# di.net
KiCad netlist of a schematic drawn in Altium Designer
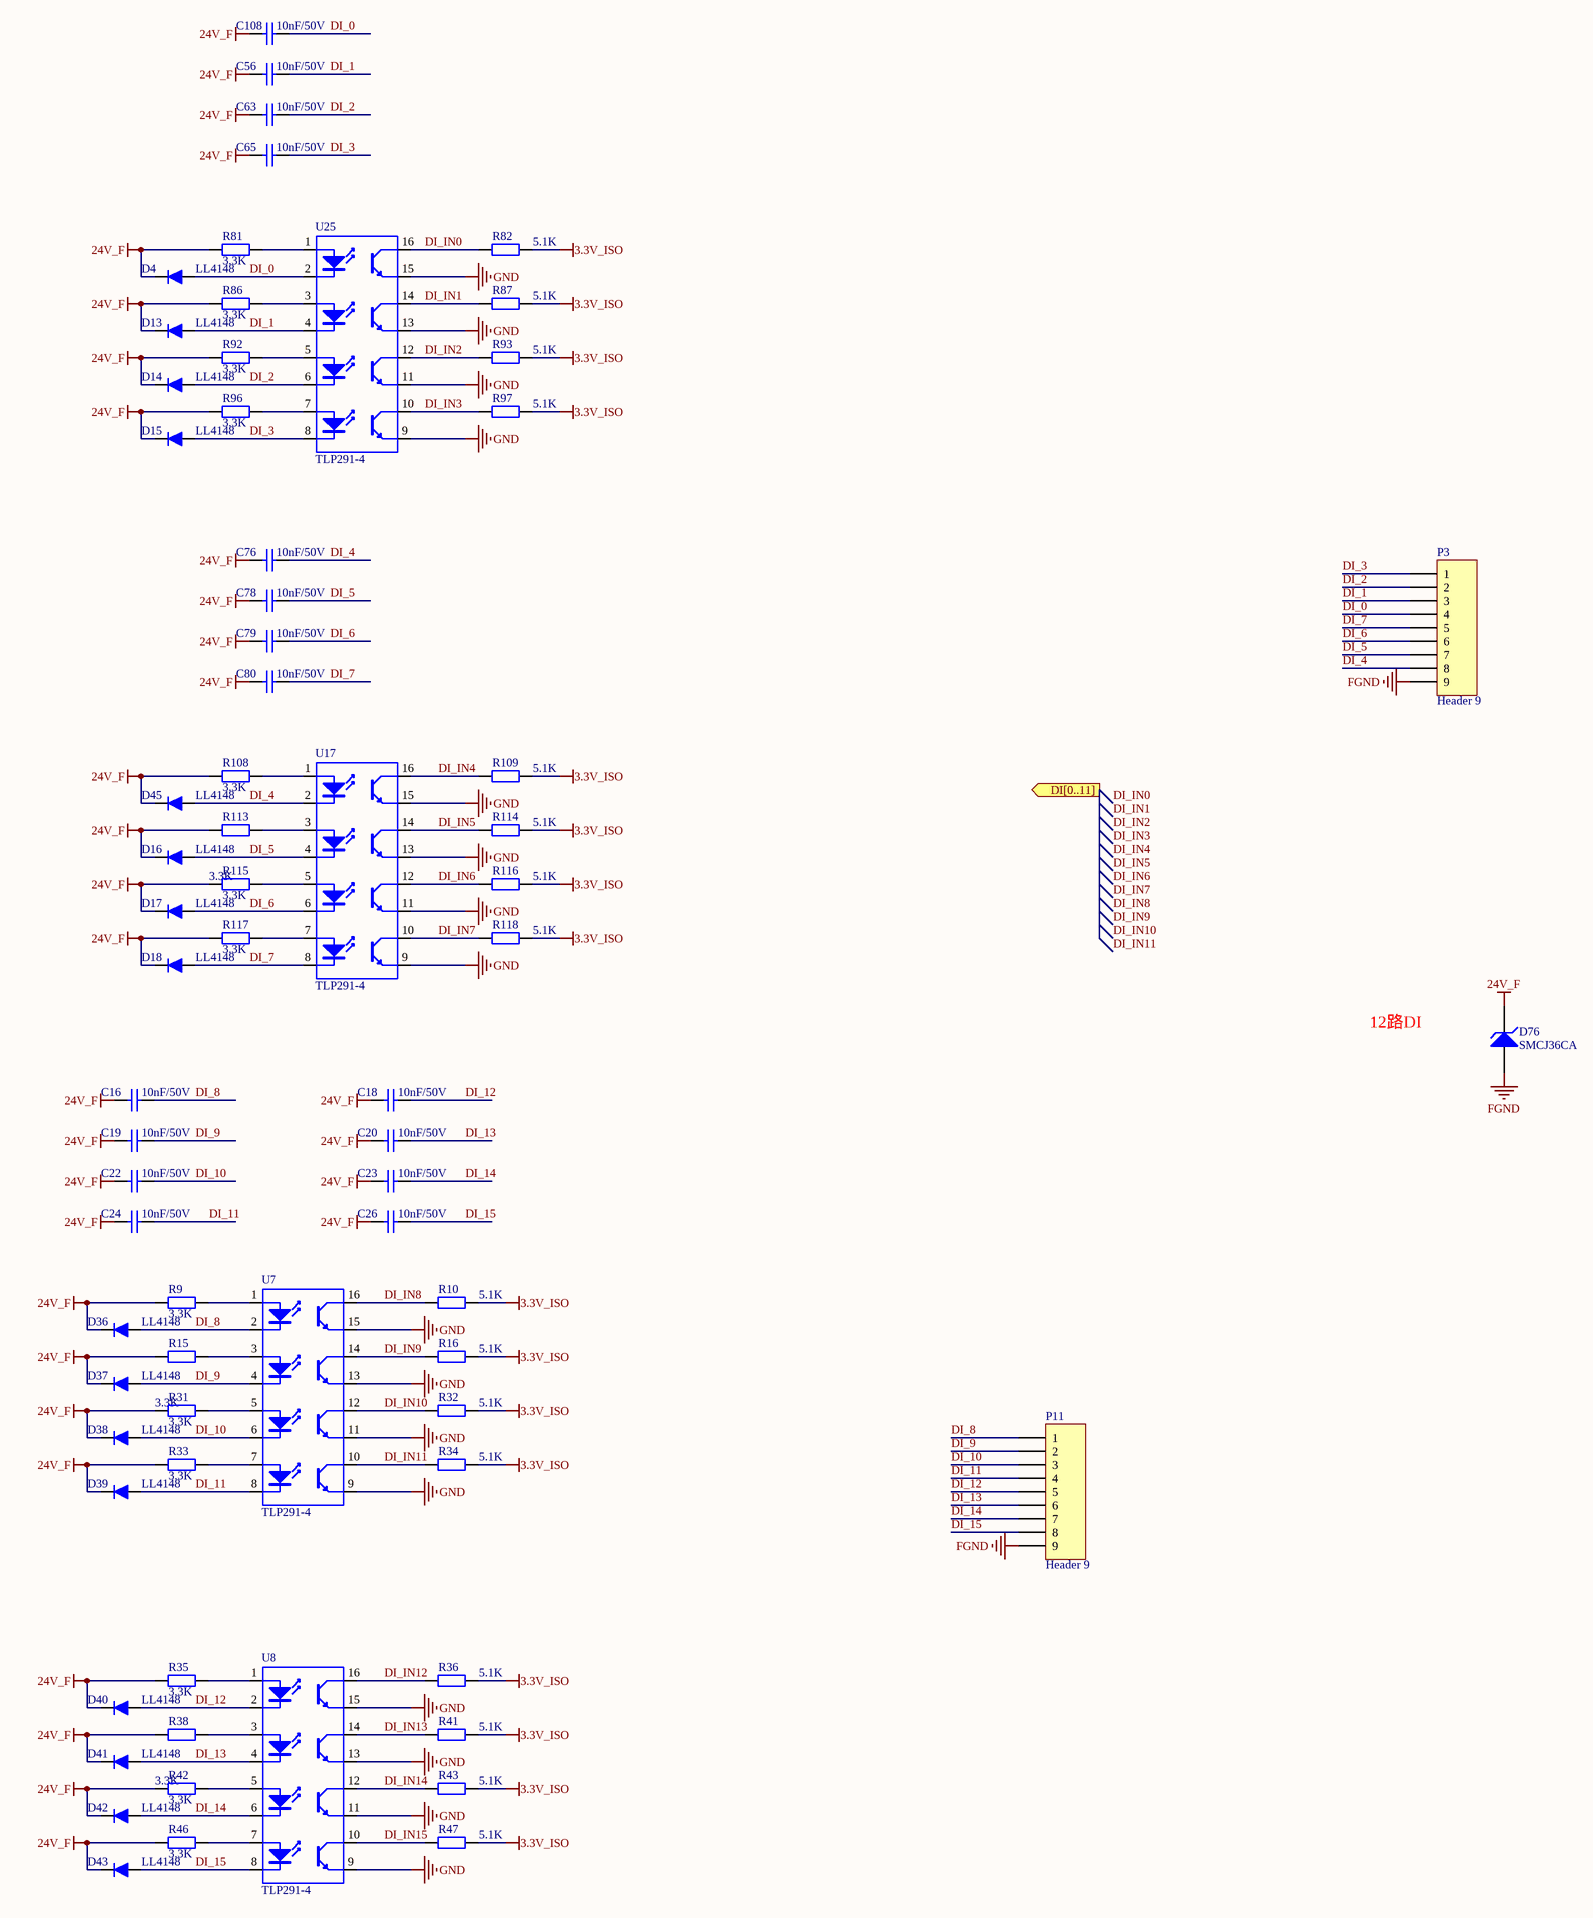
[diagram p0: di.SchDoc]

(export (version "E")
  (design (tool "Eeschema 10.0.6"))
  (components
    (comp (ref "C16")
      (value "10nF/50V")
      (footprint "0603C")
      (description "Capacitor")
      (fields (field (name "PUBLISHER") "Altium Limited"))
      (libsource (lib "Miscellaneous Devices") (part "Cap"))
    )
    (comp (ref "C18")
      (value "10nF/50V")
      (footprint "0603C")
      (description "Capacitor")
      (fields (field (name "PUBLISHER") "Altium Limited"))
      (libsource (lib "Miscellaneous Devices") (part "Cap"))
    )
    (comp (ref "C19")
      (value "10nF/50V")
      (footprint "0603C")
      (description "Capacitor")
      (fields (field (name "PUBLISHER") "Altium Limited"))
      (libsource (lib "Miscellaneous Devices") (part "Cap"))
    )
    (comp (ref "C20")
      (value "10nF/50V")
      (footprint "0603C")
      (description "Capacitor")
      (fields (field (name "PUBLISHER") "Altium Limited"))
      (libsource (lib "Miscellaneous Devices") (part "Cap"))
    )
    (comp (ref "C22")
      (value "10nF/50V")
      (footprint "0603C")
      (description "Capacitor")
      (fields (field (name "PUBLISHER") "Altium Limited"))
      (libsource (lib "Miscellaneous Devices") (part "Cap"))
    )
    (comp (ref "C23")
      (value "10nF/50V")
      (footprint "0603C")
      (description "Capacitor")
      (fields (field (name "PUBLISHER") "Altium Limited"))
      (libsource (lib "Miscellaneous Devices") (part "Cap"))
    )
    (comp (ref "C24")
      (value "10nF/50V")
      (footprint "0603C")
      (description "Capacitor")
      (fields (field (name "PUBLISHER") "Altium Limited"))
      (libsource (lib "Miscellaneous Devices") (part "Cap"))
    )
    (comp (ref "C26")
      (value "10nF/50V")
      (footprint "0603C")
      (description "Capacitor")
      (fields (field (name "PUBLISHER") "Altium Limited"))
      (libsource (lib "Miscellaneous Devices") (part "Cap"))
    )
    (comp (ref "C56")
      (value "10nF/50V")
      (footprint "0603C")
      (description "Capacitor")
      (fields (field (name "PUBLISHER") "Altium Limited"))
      (libsource (lib "Miscellaneous Devices") (part "Cap"))
    )
    (comp (ref "C63")
      (value "10nF/50V")
      (footprint "0603C")
      (description "Capacitor")
      (fields (field (name "PUBLISHER") "Altium Limited"))
      (libsource (lib "Miscellaneous Devices") (part "Cap"))
    )
    (comp (ref "C65")
      (value "10nF/50V")
      (footprint "0603C")
      (description "Capacitor")
      (fields (field (name "PUBLISHER") "Altium Limited"))
      (libsource (lib "Miscellaneous Devices") (part "Cap"))
    )
    (comp (ref "C76")
      (value "10nF/50V")
      (footprint "0603C")
      (description "Capacitor")
      (fields (field (name "PUBLISHER") "Altium Limited"))
      (libsource (lib "Miscellaneous Devices") (part "Cap"))
    )
    (comp (ref "C78")
      (value "10nF/50V")
      (footprint "0603C")
      (description "Capacitor")
      (fields (field (name "PUBLISHER") "Altium Limited"))
      (libsource (lib "Miscellaneous Devices") (part "Cap"))
    )
    (comp (ref "C79")
      (value "10nF/50V")
      (footprint "0603C")
      (description "Capacitor")
      (fields (field (name "PUBLISHER") "Altium Limited"))
      (libsource (lib "Miscellaneous Devices") (part "Cap"))
    )
    (comp (ref "C80")
      (value "10nF/50V")
      (footprint "0603C")
      (description "Capacitor")
      (fields (field (name "PUBLISHER") "Altium Limited"))
      (libsource (lib "Miscellaneous Devices") (part "Cap"))
    )
    (comp (ref "C108")
      (value "10nF/50V")
      (footprint "0603C")
      (description "Capacitor")
      (fields (field (name "PUBLISHER") "Altium Limited"))
      (libsource (lib "Miscellaneous Devices") (part "Cap"))
    )
    (comp (ref "D4")
      (value "LL4148")
      (footprint "DO-213AB/LL34/MiniMELF")
      (description "VISHAY,LL4148,圆柱体MiniMELF100V/2A,ROHS")
      (libsource (lib "Device2018") (part "LL4148"))
    )
    (comp (ref "D13")
      (value "LL4148")
      (footprint "DO-213AB/LL34/MiniMELF")
      (description "VISHAY,LL4148,圆柱体MiniMELF100V/2A,ROHS")
      (libsource (lib "Device2018") (part "LL4148"))
    )
    (comp (ref "D14")
      (value "LL4148")
      (footprint "DO-213AB/LL34/MiniMELF")
      (description "VISHAY,LL4148,圆柱体MiniMELF100V/2A,ROHS")
      (libsource (lib "Device2018") (part "LL4148"))
    )
    (comp (ref "D15")
      (value "LL4148")
      (footprint "DO-213AB/LL34/MiniMELF")
      (description "VISHAY,LL4148,圆柱体MiniMELF100V/2A,ROHS")
      (libsource (lib "Device2018") (part "LL4148"))
    )
    (comp (ref "D16")
      (value "LL4148")
      (footprint "DO-213AB/LL34/MiniMELF")
      (description "VISHAY,LL4148,圆柱体MiniMELF100V/2A,ROHS")
      (libsource (lib "Device2018") (part "LL4148"))
    )
    (comp (ref "D17")
      (value "LL4148")
      (footprint "DO-213AB/LL34/MiniMELF")
      (description "VISHAY,LL4148,圆柱体MiniMELF100V/2A,ROHS")
      (libsource (lib "Device2018") (part "LL4148"))
    )
    (comp (ref "D18")
      (value "LL4148")
      (footprint "DO-213AB/LL34/MiniMELF")
      (description "VISHAY,LL4148,圆柱体MiniMELF100V/2A,ROHS")
      (libsource (lib "Device2018") (part "LL4148"))
    )
    (comp (ref "D36")
      (value "LL4148")
      (footprint "DO-213AB/LL34/MiniMELF")
      (description "VISHAY,LL4148,圆柱体MiniMELF100V/2A,ROHS")
      (libsource (lib "Device2018") (part "LL4148"))
    )
    (comp (ref "D37")
      (value "LL4148")
      (footprint "DO-213AB/LL34/MiniMELF")
      (description "VISHAY,LL4148,圆柱体MiniMELF100V/2A,ROHS")
      (libsource (lib "Device2018") (part "LL4148"))
    )
    (comp (ref "D38")
      (value "LL4148")
      (footprint "DO-213AB/LL34/MiniMELF")
      (description "VISHAY,LL4148,圆柱体MiniMELF100V/2A,ROHS")
      (libsource (lib "Device2018") (part "LL4148"))
    )
    (comp (ref "D39")
      (value "LL4148")
      (footprint "DO-213AB/LL34/MiniMELF")
      (description "VISHAY,LL4148,圆柱体MiniMELF100V/2A,ROHS")
      (libsource (lib "Device2018") (part "LL4148"))
    )
    (comp (ref "D40")
      (value "LL4148")
      (footprint "DO-213AB/LL34/MiniMELF")
      (description "VISHAY,LL4148,圆柱体MiniMELF100V/2A,ROHS")
      (libsource (lib "Device2018") (part "LL4148"))
    )
    (comp (ref "D41")
      (value "LL4148")
      (footprint "DO-213AB/LL34/MiniMELF")
      (description "VISHAY,LL4148,圆柱体MiniMELF100V/2A,ROHS")
      (libsource (lib "Device2018") (part "LL4148"))
    )
    (comp (ref "D42")
      (value "LL4148")
      (footprint "DO-213AB/LL34/MiniMELF")
      (description "VISHAY,LL4148,圆柱体MiniMELF100V/2A,ROHS")
      (libsource (lib "Device2018") (part "LL4148"))
    )
    (comp (ref "D43")
      (value "LL4148")
      (footprint "DO-213AB/LL34/MiniMELF")
      (description "VISHAY,LL4148,圆柱体MiniMELF100V/2A,ROHS")
      (libsource (lib "Device2018") (part "LL4148"))
    )
    (comp (ref "D45")
      (value "LL4148")
      (footprint "DO-213AB/LL34/MiniMELF")
      (description "VISHAY,LL4148,圆柱体MiniMELF100V/2A,ROHS")
      (libsource (lib "Device2018") (part "LL4148"))
    )
    (comp (ref "D76")
      (value "SMCJ36CA")
      (footprint "smc")
      (description "SMBJ36CA")
      (fields (field (name "PUBLISHER") "Altium Limited"))
      (libsource (lib "Miscellaneous Devices") (part "D Zener"))
    )
    (comp (ref "P3")
      (value "Header 9")
      (footprint "2ETYR-5.08-09P-14-100")
      (description "Header, 9-Pin")
      (fields (field (name "PUBLISHER") "Altium Limited"))
      (libsource (lib "Miscellaneous Connectors") (part "Header 9"))
    )
    (comp (ref "P11")
      (value "Header 9")
      (footprint "2ETYR-5.08-09P-14-100")
      (description "Header, 9-Pin")
      (fields (field (name "PUBLISHER") "Altium Limited"))
      (libsource (lib "Miscellaneous Connectors") (part "Header 9"))
    )
    (comp (ref "R9") (value "3.3K") (footprint "0603R") (libsource (lib "MQlibrary") (part "Res0805M")))
    (comp (ref "R10") (value "5.1K") (footprint "0603R") (libsource (lib "MQlibrary") (part "Res0805M")))
    (comp (ref "R15") (value "3.3K") (footprint "0603R") (libsource (lib "MQlibrary") (part "Res0805M")))
    (comp (ref "R16") (value "5.1K") (footprint "0603R") (libsource (lib "MQlibrary") (part "Res0805M")))
    (comp (ref "R31") (value "3.3K") (footprint "0603R") (libsource (lib "MQlibrary") (part "Res0805M")))
    (comp (ref "R32") (value "5.1K") (footprint "0603R") (libsource (lib "MQlibrary") (part "Res0805M")))
    (comp (ref "R33") (value "3.3K") (footprint "0603R") (libsource (lib "MQlibrary") (part "Res0805M")))
    (comp (ref "R34") (value "5.1K") (footprint "0603R") (libsource (lib "MQlibrary") (part "Res0805M")))
    (comp (ref "R35") (value "3.3K") (footprint "0603R") (libsource (lib "MQlibrary") (part "Res0805M")))
    (comp (ref "R36") (value "5.1K") (footprint "0603R") (libsource (lib "MQlibrary") (part "Res0805M")))
    (comp (ref "R38") (value "3.3K") (footprint "0603R") (libsource (lib "MQlibrary") (part "Res0805M")))
    (comp (ref "R41") (value "5.1K") (footprint "0603R") (libsource (lib "MQlibrary") (part "Res0805M")))
    (comp (ref "R42") (value "3.3K") (footprint "0603R") (libsource (lib "MQlibrary") (part "Res0805M")))
    (comp (ref "R43") (value "5.1K") (footprint "0603R") (libsource (lib "MQlibrary") (part "Res0805M")))
    (comp (ref "R46") (value "3.3K") (footprint "0603R") (libsource (lib "MQlibrary") (part "Res0805M")))
    (comp (ref "R47") (value "5.1K") (footprint "0603R") (libsource (lib "MQlibrary") (part "Res0805M")))
    (comp (ref "R81") (value "3.3K") (footprint "0603R") (libsource (lib "MQlibrary") (part "Res0805M")))
    (comp (ref "R82") (value "5.1K") (footprint "0603R") (libsource (lib "MQlibrary") (part "Res0805M")))
    (comp (ref "R86") (value "3.3K") (footprint "0603R") (libsource (lib "MQlibrary") (part "Res0805M")))
    (comp (ref "R87") (value "5.1K") (footprint "0603R") (libsource (lib "MQlibrary") (part "Res0805M")))
    (comp (ref "R92") (value "3.3K") (footprint "0603R") (libsource (lib "MQlibrary") (part "Res0805M")))
    (comp (ref "R93") (value "5.1K") (footprint "0603R") (libsource (lib "MQlibrary") (part "Res0805M")))
    (comp (ref "R96") (value "3.3K") (footprint "0603R") (libsource (lib "MQlibrary") (part "Res0805M")))
    (comp (ref "R97") (value "5.1K") (footprint "0603R") (libsource (lib "MQlibrary") (part "Res0805M")))
    (comp (ref "R108") (value "3.3K") (footprint "0603R") (libsource (lib "MQlibrary") (part "Res0805M")))
    (comp (ref "R109") (value "5.1K") (footprint "0603R") (libsource (lib "MQlibrary") (part "Res0805M")))
    (comp (ref "R113") (value "3.3K") (footprint "0603R") (libsource (lib "MQlibrary") (part "Res0805M")))
    (comp (ref "R114") (value "5.1K") (footprint "0603R") (libsource (lib "MQlibrary") (part "Res0805M")))
    (comp (ref "R115") (value "3.3K") (footprint "0603R") (libsource (lib "MQlibrary") (part "Res0805M")))
    (comp (ref "R116") (value "5.1K") (footprint "0603R") (libsource (lib "MQlibrary") (part "Res0805M")))
    (comp (ref "R117") (value "3.3K") (footprint "0603R") (libsource (lib "MQlibrary") (part "Res0805M")))
    (comp (ref "R118") (value "5.1K") (footprint "0603R") (libsource (lib "MQlibrary") (part "Res0805M")))
    (comp (ref "U7") (value "TLP291-4") (footprint "SOP16-T") (libsource (lib "DI16") (part "TLP281-4")))
    (comp (ref "U8") (value "TLP291-4") (footprint "SOP16-T") (libsource (lib "DI16") (part "TLP281-4")))
    (comp (ref "U17") (value "TLP291-4") (footprint "SOP16-T") (libsource (lib "DI16") (part "TLP281-4")))
    (comp (ref "U25") (value "TLP291-4") (footprint "SOP16-T") (libsource (lib "DI16") (part "TLP281-4")))
  )
  (nets
    (net (code "14") (name "/DI_0") (class "Default")
      (node (ref "C108") (pin "2") (pinfunction "2_2") (pintype "passive"))
      (node (ref "D4") (pin "1") (pinfunction "2_1") (pintype "passive"))
      (node (ref "P3") (pin "4") (pinfunction "4_4") (pintype "passive"))
      (node (ref "U25") (pin "2") (pinfunction "K_2") (pintype "passive"))
    )
    (net (code "15") (name "/DI_1") (class "Default")
      (node (ref "C56") (pin "2") (pinfunction "2_2") (pintype "passive"))
      (node (ref "D13") (pin "1") (pinfunction "2_1") (pintype "passive"))
      (node (ref "P3") (pin "3") (pinfunction "3_3") (pintype "passive"))
      (node (ref "U25") (pin "4") (pinfunction "K_4") (pintype "passive"))
    )
    (net (code "16") (name "/DI_2") (class "Default")
      (node (ref "C63") (pin "2") (pinfunction "2_2") (pintype "passive"))
      (node (ref "D14") (pin "1") (pinfunction "2_1") (pintype "passive"))
      (node (ref "P3") (pin "2") (pinfunction "2_2") (pintype "passive"))
      (node (ref "U25") (pin "6") (pinfunction "K_6") (pintype "passive"))
    )
    (net (code "17") (name "/DI_3") (class "Default")
      (node (ref "C65") (pin "2") (pinfunction "2_2") (pintype "passive"))
      (node (ref "D15") (pin "1") (pinfunction "2_1") (pintype "passive"))
      (node (ref "P3") (pin "1") (pinfunction "1_1") (pintype "passive"))
      (node (ref "U25") (pin "8") (pinfunction "K_8") (pintype "passive"))
    )
    (net (code "18") (name "/DI_4") (class "Default")
      (node (ref "C76") (pin "2") (pinfunction "2_2") (pintype "passive"))
      (node (ref "D45") (pin "1") (pinfunction "2_1") (pintype "passive"))
      (node (ref "P3") (pin "8") (pinfunction "8_8") (pintype "passive"))
      (node (ref "U17") (pin "2") (pinfunction "K_2") (pintype "passive"))
    )
    (net (code "19") (name "/DI_5") (class "Default")
      (node (ref "C78") (pin "2") (pinfunction "2_2") (pintype "passive"))
      (node (ref "D16") (pin "1") (pinfunction "2_1") (pintype "passive"))
      (node (ref "P3") (pin "7") (pinfunction "7_7") (pintype "passive"))
      (node (ref "U17") (pin "4") (pinfunction "K_4") (pintype "passive"))
    )
    (net (code "20") (name "/DI_6") (class "Default")
      (node (ref "C79") (pin "2") (pinfunction "2_2") (pintype "passive"))
      (node (ref "D17") (pin "1") (pinfunction "2_1") (pintype "passive"))
      (node (ref "P3") (pin "6") (pinfunction "6_6") (pintype "passive"))
      (node (ref "U17") (pin "6") (pinfunction "K_6") (pintype "passive"))
    )
    (net (code "21") (name "/DI_7") (class "Default")
      (node (ref "C80") (pin "2") (pinfunction "2_2") (pintype "passive"))
      (node (ref "D18") (pin "1") (pinfunction "2_1") (pintype "passive"))
      (node (ref "P3") (pin "5") (pinfunction "5_5") (pintype "passive"))
      (node (ref "U17") (pin "8") (pinfunction "K_8") (pintype "passive"))
    )
    (net (code "22") (name "/DI_8") (class "Default")
      (node (ref "C16") (pin "2") (pinfunction "2_2") (pintype "passive"))
      (node (ref "D36") (pin "1") (pinfunction "2_1") (pintype "passive"))
      (node (ref "P11") (pin "1") (pinfunction "1_1") (pintype "passive"))
      (node (ref "U7") (pin "2") (pinfunction "K_2") (pintype "passive"))
    )
    (net (code "23") (name "/DI_9") (class "Default")
      (node (ref "C19") (pin "2") (pinfunction "2_2") (pintype "passive"))
      (node (ref "D37") (pin "1") (pinfunction "2_1") (pintype "passive"))
      (node (ref "P11") (pin "2") (pinfunction "2_2") (pintype "passive"))
      (node (ref "U7") (pin "4") (pinfunction "K_4") (pintype "passive"))
    )
    (net (code "24") (name "/DI_10") (class "Default")
      (node (ref "C22") (pin "2") (pinfunction "2_2") (pintype "passive"))
      (node (ref "D38") (pin "1") (pinfunction "2_1") (pintype "passive"))
      (node (ref "P11") (pin "3") (pinfunction "3_3") (pintype "passive"))
      (node (ref "U7") (pin "6") (pinfunction "K_6") (pintype "passive"))
    )
    (net (code "25") (name "/DI_11") (class "Default")
      (node (ref "C24") (pin "2") (pinfunction "2_2") (pintype "passive"))
      (node (ref "D39") (pin "1") (pinfunction "2_1") (pintype "passive"))
      (node (ref "P11") (pin "4") (pinfunction "4_4") (pintype "passive"))
      (node (ref "U7") (pin "8") (pinfunction "K_8") (pintype "passive"))
    )
    (net (code "26") (name "/DI_12") (class "Default")
      (node (ref "C18") (pin "2") (pinfunction "2_2") (pintype "passive"))
      (node (ref "D40") (pin "1") (pinfunction "2_1") (pintype "passive"))
      (node (ref "P11") (pin "5") (pinfunction "5_5") (pintype "passive"))
      (node (ref "U8") (pin "2") (pinfunction "K_2") (pintype "passive"))
    )
    (net (code "27") (name "/DI_13") (class "Default")
      (node (ref "C20") (pin "2") (pinfunction "2_2") (pintype "passive"))
      (node (ref "D41") (pin "1") (pinfunction "2_1") (pintype "passive"))
      (node (ref "P11") (pin "6") (pinfunction "6_6") (pintype "passive"))
      (node (ref "U8") (pin "4") (pinfunction "K_4") (pintype "passive"))
    )
    (net (code "28") (name "/DI_14") (class "Default")
      (node (ref "C23") (pin "2") (pinfunction "2_2") (pintype "passive"))
      (node (ref "D42") (pin "1") (pinfunction "2_1") (pintype "passive"))
      (node (ref "P11") (pin "7") (pinfunction "7_7") (pintype "passive"))
      (node (ref "U8") (pin "6") (pinfunction "K_6") (pintype "passive"))
    )
    (net (code "29") (name "/DI_15") (class "Default")
      (node (ref "C26") (pin "2") (pinfunction "2_2") (pintype "passive"))
      (node (ref "D43") (pin "1") (pinfunction "2_1") (pintype "passive"))
      (node (ref "P11") (pin "8") (pinfunction "8_8") (pintype "passive"))
      (node (ref "U8") (pin "8") (pinfunction "K_8") (pintype "passive"))
    )
    (net (code "30") (name "/DI_IN0") (class "Default")
      (node (ref "R82") (pin "2") (pinfunction "2_2") (pintype "passive"))
      (node (ref "U25") (pin "16") (pinfunction "C_16") (pintype "passive"))
    )
    (net (code "31") (name "/DI_IN1") (class "Default")
      (node (ref "R87") (pin "2") (pinfunction "2_2") (pintype "passive"))
      (node (ref "U25") (pin "14") (pinfunction "C_14") (pintype "passive"))
    )
    (net (code "32") (name "/DI_IN2") (class "Default")
      (node (ref "R93") (pin "2") (pinfunction "2_2") (pintype "passive"))
      (node (ref "U25") (pin "12") (pinfunction "C_12") (pintype "passive"))
    )
    (net (code "33") (name "/DI_IN3") (class "Default")
      (node (ref "R97") (pin "2") (pinfunction "2_2") (pintype "passive"))
      (node (ref "U25") (pin "10") (pinfunction "C_10") (pintype "passive"))
    )
    (net (code "34") (name "/DI_IN4") (class "Default")
      (node (ref "R109") (pin "2") (pinfunction "2_2") (pintype "passive"))
      (node (ref "U17") (pin "16") (pinfunction "C_16") (pintype "passive"))
    )
    (net (code "35") (name "/DI_IN5") (class "Default")
      (node (ref "R114") (pin "2") (pinfunction "2_2") (pintype "passive"))
      (node (ref "U17") (pin "14") (pinfunction "C_14") (pintype "passive"))
    )
    (net (code "36") (name "/DI_IN6") (class "Default")
      (node (ref "R116") (pin "2") (pinfunction "2_2") (pintype "passive"))
      (node (ref "U17") (pin "12") (pinfunction "C_12") (pintype "passive"))
    )
    (net (code "37") (name "/DI_IN7") (class "Default")
      (node (ref "R118") (pin "2") (pinfunction "2_2") (pintype "passive"))
      (node (ref "U17") (pin "10") (pinfunction "C_10") (pintype "passive"))
    )
    (net (code "38") (name "/DI_IN8") (class "Default")
      (node (ref "R10") (pin "2") (pinfunction "2_2") (pintype "passive"))
      (node (ref "U7") (pin "16") (pinfunction "C_16") (pintype "passive"))
    )
    (net (code "39") (name "/DI_IN9") (class "Default")
      (node (ref "R16") (pin "2") (pinfunction "2_2") (pintype "passive"))
      (node (ref "U7") (pin "14") (pinfunction "C_14") (pintype "passive"))
    )
    (net (code "40") (name "/DI_IN10") (class "Default")
      (node (ref "R32") (pin "2") (pinfunction "2_2") (pintype "passive"))
      (node (ref "U7") (pin "12") (pinfunction "C_12") (pintype "passive"))
    )
    (net (code "41") (name "/DI_IN11") (class "Default")
      (node (ref "R34") (pin "2") (pinfunction "2_2") (pintype "passive"))
      (node (ref "U7") (pin "10") (pinfunction "C_10") (pintype "passive"))
    )
    (net (code "42") (name "/DI_IN12") (class "Default")
      (node (ref "R36") (pin "2") (pinfunction "2_2") (pintype "passive"))
      (node (ref "U8") (pin "16") (pinfunction "C_16") (pintype "passive"))
    )
    (net (code "43") (name "/DI_IN13") (class "Default")
      (node (ref "R41") (pin "2") (pinfunction "2_2") (pintype "passive"))
      (node (ref "U8") (pin "14") (pinfunction "C_14") (pintype "passive"))
    )
    (net (code "44") (name "/DI_IN14") (class "Default")
      (node (ref "R43") (pin "2") (pinfunction "2_2") (pintype "passive"))
      (node (ref "U8") (pin "12") (pinfunction "C_12") (pintype "passive"))
    )
    (net (code "45") (name "/DI_IN15") (class "Default")
      (node (ref "R47") (pin "2") (pinfunction "2_2") (pintype "passive"))
      (node (ref "U8") (pin "10") (pinfunction "C_10") (pintype "passive"))
    )
    (net (code "46") (name "3.3V_ISO") (class "Default")
      (node (ref "R10") (pin "1") (pinfunction "1_1") (pintype "passive"))
      (node (ref "R109") (pin "1") (pinfunction "1_1") (pintype "passive"))
      (node (ref "R114") (pin "1") (pinfunction "1_1") (pintype "passive"))
      (node (ref "R116") (pin "1") (pinfunction "1_1") (pintype "passive"))
      (node (ref "R118") (pin "1") (pinfunction "1_1") (pintype "passive"))
      (node (ref "R16") (pin "1") (pinfunction "1_1") (pintype "passive"))
      (node (ref "R32") (pin "1") (pinfunction "1_1") (pintype "passive"))
      (node (ref "R34") (pin "1") (pinfunction "1_1") (pintype "passive"))
      (node (ref "R36") (pin "1") (pinfunction "1_1") (pintype "passive"))
      (node (ref "R41") (pin "1") (pinfunction "1_1") (pintype "passive"))
      (node (ref "R43") (pin "1") (pinfunction "1_1") (pintype "passive"))
      (node (ref "R47") (pin "1") (pinfunction "1_1") (pintype "passive"))
      (node (ref "R82") (pin "1") (pinfunction "1_1") (pintype "passive"))
      (node (ref "R87") (pin "1") (pinfunction "1_1") (pintype "passive"))
      (node (ref "R93") (pin "1") (pinfunction "1_1") (pintype "passive"))
      (node (ref "R97") (pin "1") (pinfunction "1_1") (pintype "passive"))
    )
    (net (code "47") (name "24V_F") (class "Default")
      (node (ref "C108") (pin "1") (pinfunction "1_1") (pintype "passive"))
      (node (ref "C16") (pin "1") (pinfunction "1_1") (pintype "passive"))
      (node (ref "C18") (pin "1") (pinfunction "1_1") (pintype "passive"))
      (node (ref "C19") (pin "1") (pinfunction "1_1") (pintype "passive"))
      (node (ref "C20") (pin "1") (pinfunction "1_1") (pintype "passive"))
      (node (ref "C22") (pin "1") (pinfunction "1_1") (pintype "passive"))
      (node (ref "C23") (pin "1") (pinfunction "1_1") (pintype "passive"))
      (node (ref "C24") (pin "1") (pinfunction "1_1") (pintype "passive"))
      (node (ref "C26") (pin "1") (pinfunction "1_1") (pintype "passive"))
      (node (ref "C56") (pin "1") (pinfunction "1_1") (pintype "passive"))
      (node (ref "C63") (pin "1") (pinfunction "1_1") (pintype "passive"))
      (node (ref "C65") (pin "1") (pinfunction "1_1") (pintype "passive"))
      (node (ref "C76") (pin "1") (pinfunction "1_1") (pintype "passive"))
      (node (ref "C78") (pin "1") (pinfunction "1_1") (pintype "passive"))
      (node (ref "C79") (pin "1") (pinfunction "1_1") (pintype "passive"))
      (node (ref "C80") (pin "1") (pinfunction "1_1") (pintype "passive"))
      (node (ref "D13") (pin "2") (pinfunction "1_2") (pintype "passive"))
      (node (ref "D14") (pin "2") (pinfunction "1_2") (pintype "passive"))
      (node (ref "D15") (pin "2") (pinfunction "1_2") (pintype "passive"))
      (node (ref "D16") (pin "2") (pinfunction "1_2") (pintype "passive"))
      (node (ref "D17") (pin "2") (pinfunction "1_2") (pintype "passive"))
      (node (ref "D18") (pin "2") (pinfunction "1_2") (pintype "passive"))
      (node (ref "D36") (pin "2") (pinfunction "1_2") (pintype "passive"))
      (node (ref "D37") (pin "2") (pinfunction "1_2") (pintype "passive"))
      (node (ref "D38") (pin "2") (pinfunction "1_2") (pintype "passive"))
      (node (ref "D39") (pin "2") (pinfunction "1_2") (pintype "passive"))
      (node (ref "D4") (pin "2") (pinfunction "1_2") (pintype "passive"))
      (node (ref "D40") (pin "2") (pinfunction "1_2") (pintype "passive"))
      (node (ref "D41") (pin "2") (pinfunction "1_2") (pintype "passive"))
      (node (ref "D42") (pin "2") (pinfunction "1_2") (pintype "passive"))
      (node (ref "D43") (pin "2") (pinfunction "1_2") (pintype "passive"))
      (node (ref "D45") (pin "2") (pinfunction "1_2") (pintype "passive"))
      (node (ref "D76") (pin "2") (pinfunction "K_2") (pintype "passive"))
      (node (ref "R108") (pin "2") (pinfunction "2_2") (pintype "passive"))
      (node (ref "R113") (pin "2") (pinfunction "2_2") (pintype "passive"))
      (node (ref "R115") (pin "2") (pinfunction "2_2") (pintype "passive"))
      (node (ref "R117") (pin "2") (pinfunction "2_2") (pintype "passive"))
      (node (ref "R15") (pin "2") (pinfunction "2_2") (pintype "passive"))
      (node (ref "R31") (pin "2") (pinfunction "2_2") (pintype "passive"))
      (node (ref "R33") (pin "2") (pinfunction "2_2") (pintype "passive"))
      (node (ref "R35") (pin "2") (pinfunction "2_2") (pintype "passive"))
      (node (ref "R38") (pin "2") (pinfunction "2_2") (pintype "passive"))
      (node (ref "R42") (pin "2") (pinfunction "2_2") (pintype "passive"))
      (node (ref "R46") (pin "2") (pinfunction "2_2") (pintype "passive"))
      (node (ref "R81") (pin "2") (pinfunction "2_2") (pintype "passive"))
      (node (ref "R86") (pin "2") (pinfunction "2_2") (pintype "passive"))
      (node (ref "R9") (pin "2") (pinfunction "2_2") (pintype "passive"))
      (node (ref "R92") (pin "2") (pinfunction "2_2") (pintype "passive"))
      (node (ref "R96") (pin "2") (pinfunction "2_2") (pintype "passive"))
    )
    (net (code "48") (name "FGND") (class "Default")
      (node (ref "D76") (pin "1") (pinfunction "A_1") (pintype "passive"))
      (node (ref "P11") (pin "9") (pinfunction "9_9") (pintype "passive"))
      (node (ref "P3") (pin "9") (pinfunction "9_9") (pintype "passive"))
    )
    (net (code "49") (name "GND") (class "Default")
      (node (ref "U17") (pin "11") (pinfunction "E_11") (pintype "passive"))
      (node (ref "U17") (pin "13") (pinfunction "E_13") (pintype "passive"))
      (node (ref "U17") (pin "15") (pinfunction "E_15") (pintype "passive"))
      (node (ref "U17") (pin "9") (pinfunction "E_9") (pintype "passive"))
      (node (ref "U25") (pin "11") (pinfunction "E_11") (pintype "passive"))
      (node (ref "U25") (pin "13") (pinfunction "E_13") (pintype "passive"))
      (node (ref "U25") (pin "15") (pinfunction "E_15") (pintype "passive"))
      (node (ref "U25") (pin "9") (pinfunction "E_9") (pintype "passive"))
      (node (ref "U7") (pin "11") (pinfunction "E_11") (pintype "passive"))
      (node (ref "U7") (pin "13") (pinfunction "E_13") (pintype "passive"))
      (node (ref "U7") (pin "15") (pinfunction "E_15") (pintype "passive"))
      (node (ref "U7") (pin "9") (pinfunction "E_9") (pintype "passive"))
      (node (ref "U8") (pin "11") (pinfunction "E_11") (pintype "passive"))
      (node (ref "U8") (pin "13") (pinfunction "E_13") (pintype "passive"))
      (node (ref "U8") (pin "15") (pinfunction "E_15") (pintype "passive"))
      (node (ref "U8") (pin "9") (pinfunction "E_9") (pintype "passive"))
    )
    (net (code "50") (name "Net-(R9-Pad1)") (class "Default")
      (node (ref "R9") (pin "1") (pinfunction "1_1") (pintype "passive"))
      (node (ref "U7") (pin "1") (pinfunction "A_1") (pintype "passive"))
    )
    (net (code "51") (name "Net-(R15-Pad1)") (class "Default")
      (node (ref "R15") (pin "1") (pinfunction "1_1") (pintype "passive"))
      (node (ref "U7") (pin "3") (pinfunction "A_3") (pintype "passive"))
    )
    (net (code "52") (name "Net-(R31-Pad1)") (class "Default")
      (node (ref "R31") (pin "1") (pinfunction "1_1") (pintype "passive"))
      (node (ref "U7") (pin "5") (pinfunction "A_5") (pintype "passive"))
    )
    (net (code "53") (name "Net-(R33-Pad1)") (class "Default")
      (node (ref "R33") (pin "1") (pinfunction "1_1") (pintype "passive"))
      (node (ref "U7") (pin "7") (pinfunction "A_7") (pintype "passive"))
    )
    (net (code "54") (name "Net-(R35-Pad1)") (class "Default")
      (node (ref "R35") (pin "1") (pinfunction "1_1") (pintype "passive"))
      (node (ref "U8") (pin "1") (pinfunction "A_1") (pintype "passive"))
    )
    (net (code "55") (name "Net-(R38-Pad1)") (class "Default")
      (node (ref "R38") (pin "1") (pinfunction "1_1") (pintype "passive"))
      (node (ref "U8") (pin "3") (pinfunction "A_3") (pintype "passive"))
    )
    (net (code "56") (name "Net-(R42-Pad1)") (class "Default")
      (node (ref "R42") (pin "1") (pinfunction "1_1") (pintype "passive"))
      (node (ref "U8") (pin "5") (pinfunction "A_5") (pintype "passive"))
    )
    (net (code "57") (name "Net-(R46-Pad1)") (class "Default")
      (node (ref "R46") (pin "1") (pinfunction "1_1") (pintype "passive"))
      (node (ref "U8") (pin "7") (pinfunction "A_7") (pintype "passive"))
    )
    (net (code "58") (name "Net-(R81-Pad1)") (class "Default")
      (node (ref "R81") (pin "1") (pinfunction "1_1") (pintype "passive"))
      (node (ref "U25") (pin "1") (pinfunction "A_1") (pintype "passive"))
    )
    (net (code "59") (name "Net-(R86-Pad1)") (class "Default")
      (node (ref "R86") (pin "1") (pinfunction "1_1") (pintype "passive"))
      (node (ref "U25") (pin "3") (pinfunction "A_3") (pintype "passive"))
    )
    (net (code "60") (name "Net-(R92-Pad1)") (class "Default")
      (node (ref "R92") (pin "1") (pinfunction "1_1") (pintype "passive"))
      (node (ref "U25") (pin "5") (pinfunction "A_5") (pintype "passive"))
    )
    (net (code "61") (name "Net-(R96-Pad1)") (class "Default")
      (node (ref "R96") (pin "1") (pinfunction "1_1") (pintype "passive"))
      (node (ref "U25") (pin "7") (pinfunction "A_7") (pintype "passive"))
    )
    (net (code "62") (name "Net-(R108-Pad1)") (class "Default")
      (node (ref "R108") (pin "1") (pinfunction "1_1") (pintype "passive"))
      (node (ref "U17") (pin "1") (pinfunction "A_1") (pintype "passive"))
    )
    (net (code "63") (name "Net-(R113-Pad1)") (class "Default")
      (node (ref "R113") (pin "1") (pinfunction "1_1") (pintype "passive"))
      (node (ref "U17") (pin "3") (pinfunction "A_3") (pintype "passive"))
    )
    (net (code "64") (name "Net-(R115-Pad1)") (class "Default")
      (node (ref "R115") (pin "1") (pinfunction "1_1") (pintype "passive"))
      (node (ref "U17") (pin "5") (pinfunction "A_5") (pintype "passive"))
    )
    (net (code "65") (name "Net-(R117-Pad1)") (class "Default")
      (node (ref "R117") (pin "1") (pinfunction "1_1") (pintype "passive"))
      (node (ref "U17") (pin "7") (pinfunction "A_7") (pintype "passive"))
    )
  )
)
